# NRF24L01.net
KiCad netlist of a schematic drawn in Altium Designer
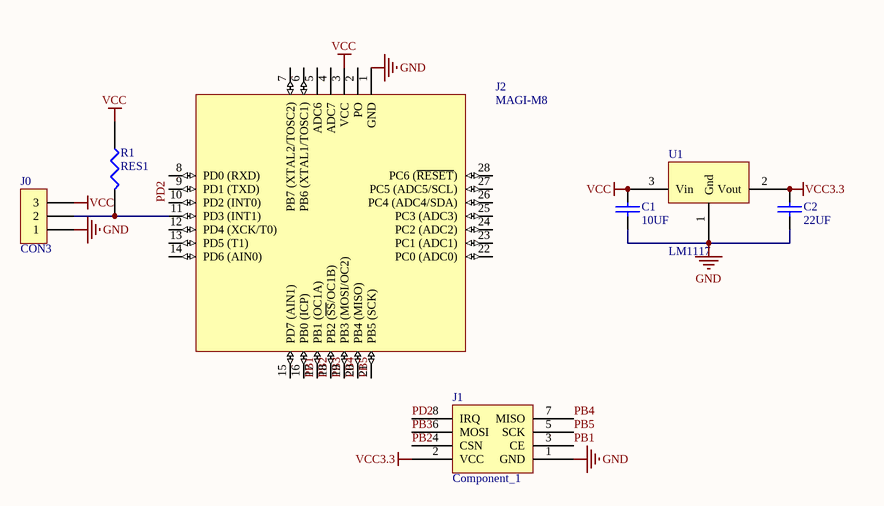
[diagram p0: NRF24L01.SchDoc]

(export (version "E")
  (design (tool "Eeschema 10.0.6"))
  (components
    (comp (ref "C1")
      (value "10UF")
      (footprint "0805")
      (description "Capacitor")
      (libsource (lib "电容器") (part "CAP_1"))
    )
    (comp (ref "C2")
      (value "22UF")
      (footprint "0805")
      (description "Capacitor")
      (libsource (lib "电容器") (part "CAP_1"))
    )
    (comp (ref "J0")
      (value "CON3")
      (footprint "CON3")
      (description "Connector")
      (libsource (lib "CON系列") (part "CON3"))
    )
    (comp (ref "J1")
      (value "Component_1")
      (footprint "NRF24L01")
      (libsource (lib "NRF24L01") (part "Component_1"))
    )
    (comp (ref "J2") (value "MAGI-M8") (footprint "MAGI-M8") (libsource (lib "MAGI-M8") (part "MAGI-M8")))
    (comp (ref "R1") (value "RES1") (footprint "0805") (libsource (lib "电阻器") (part "RES1")))
    (comp (ref "U1") (value "LM1117") (footprint "SOT-223") (libsource (lib "01.常用元件1") (part "LM1117")))
  )
  (nets
    (net (code "1") (name "/PB1") (class "Default")
      (node (ref "J1") (pin "3") (pinfunction "CE_3") (pintype "passive"))
      (node (ref "J2") (pin "17") (pinfunction "PB1_(OC1A)_17") (pintype "bidirectional"))
    )
    (net (code "2") (name "/PB2") (class "Default")
      (node (ref "J1") (pin "4") (pinfunction "CSN_4") (pintype "passive"))
      (node (ref "J2") (pin "18") (pinfunction "PB2_(~{SS}/OC1B)_18") (pintype "bidirectional"))
    )
    (net (code "3") (name "/PB3") (class "Default")
      (node (ref "J1") (pin "6") (pinfunction "MOSI_6") (pintype "passive"))
      (node (ref "J2") (pin "19") (pinfunction "PB3_(MOSI/OC2)_19") (pintype "bidirectional"))
    )
    (net (code "4") (name "/PB4") (class "Default")
      (node (ref "J1") (pin "7") (pinfunction "MISO_7") (pintype "passive"))
      (node (ref "J2") (pin "20") (pinfunction "PB4_(MISO)_20") (pintype "bidirectional"))
    )
    (net (code "5") (name "/PB5") (class "Default")
      (node (ref "J1") (pin "5") (pinfunction "SCK_5") (pintype "passive"))
      (node (ref "J2") (pin "21") (pinfunction "PB5_(SCK)_21") (pintype "bidirectional"))
    )
    (net (code "6") (name "/PD2") (class "Default")
      (node (ref "J1") (pin "8") (pinfunction "IRQ_8") (pintype "passive"))
      (node (ref "J2") (pin "10") (pinfunction "PD2_(INT0)_10") (pintype "bidirectional"))
    )
    (net (code "7") (name "GND") (class "Default")
      (node (ref "C1") (pin "2") (pinfunction "2_2") (pintype "passive"))
      (node (ref "C2") (pin "2") (pinfunction "2_2") (pintype "passive"))
      (node (ref "J0") (pin "1") (pinfunction "1_1") (pintype "passive"))
      (node (ref "J1") (pin "1") (pinfunction "GND_1") (pintype "passive"))
      (node (ref "J2") (pin "1") (pinfunction "GND_1") (pintype "power_in"))
      (node (ref "U1") (pin "1") (pinfunction "Gnd_1") (pintype "passive"))
    )
    (net (code "8") (name "Net-(J2-PD3_(INT1))") (class "Default")
      (node (ref "J0") (pin "2") (pinfunction "2_2") (pintype "passive"))
      (node (ref "J2") (pin "11") (pinfunction "PD3_(INT1)_11") (pintype "bidirectional"))
      (node (ref "R1") (pin "2") (pinfunction "2_2") (pintype "passive"))
    )
    (net (code "9") (name "VCC") (class "Default")
      (node (ref "C1") (pin "1") (pinfunction "1_1") (pintype "passive"))
      (node (ref "J0") (pin "3") (pinfunction "3_3") (pintype "passive"))
      (node (ref "J2") (pin "3") (pinfunction "VCC_3") (pintype "power_in"))
      (node (ref "R1") (pin "1") (pinfunction "1_1") (pintype "passive"))
      (node (ref "U1") (pin "3") (pinfunction "Vin_3") (pintype "passive"))
    )
    (net (code "10") (name "VCC3.3") (class "Default")
      (node (ref "C2") (pin "1") (pinfunction "1_1") (pintype "passive"))
      (node (ref "J1") (pin "2") (pinfunction "VCC_2") (pintype "passive"))
      (node (ref "U1") (pin "2") (pinfunction "Vout_2") (pintype "passive"))
    )
    (net (code "11") (name "unconnected-(J2-ADC6-Pad5)") (class "Default")
      (node (ref "J2") (pin "5") (pinfunction "ADC6_5") (pintype "passive"))
    )
    (net (code "12") (name "unconnected-(J2-ADC7-Pad4)") (class "Default")
      (node (ref "J2") (pin "4") (pinfunction "ADC7_4") (pintype "passive"))
    )
    (net (code "13") (name "unconnected-(J2-PB0_(ICP)-Pad16)") (class "Default")
      (node (ref "J2") (pin "16") (pinfunction "PB0_(ICP)_16") (pintype "bidirectional"))
    )
    (net (code "14") (name "unconnected-(J2-PB6_(XTAL1{slash}TOSC1)-Pad6)") (class "Default")
      (node (ref "J2") (pin "6") (pinfunction "PB6_(XTAL1/TOSC1)_6") (pintype "bidirectional"))
    )
    (net (code "15") (name "unconnected-(J2-PB7_(XTAL2{slash}TOSC2)-Pad7)") (class "Default")
      (node (ref "J2") (pin "7") (pinfunction "PB7_(XTAL2/TOSC2)_7") (pintype "bidirectional"))
    )
    (net (code "16") (name "unconnected-(J2-PC0_(ADC0)-Pad22)") (class "Default")
      (node (ref "J2") (pin "22") (pinfunction "PC0_(ADC0)_22") (pintype "bidirectional"))
    )
    (net (code "17") (name "unconnected-(J2-PC1_(ADC1)-Pad23)") (class "Default")
      (node (ref "J2") (pin "23") (pinfunction "PC1_(ADC1)_23") (pintype "bidirectional"))
    )
    (net (code "18") (name "unconnected-(J2-PC2_(ADC2)-Pad24)") (class "Default")
      (node (ref "J2") (pin "24") (pinfunction "PC2_(ADC2)_24") (pintype "bidirectional"))
    )
    (net (code "19") (name "unconnected-(J2-PC3_(ADC3)-Pad25)") (class "Default")
      (node (ref "J2") (pin "25") (pinfunction "PC3_(ADC3)_25") (pintype "bidirectional"))
    )
    (net (code "20") (name "unconnected-(J2-PC4_(ADC4{slash}SDA)-Pad26)") (class "Default")
      (node (ref "J2") (pin "26") (pinfunction "PC4_(ADC4/SDA)_26") (pintype "bidirectional"))
    )
    (net (code "21") (name "unconnected-(J2-PC5_(ADC5{slash}SCL)-Pad27)") (class "Default")
      (node (ref "J2") (pin "27") (pinfunction "PC5_(ADC5/SCL)_27") (pintype "bidirectional"))
    )
    (net (code "22") (name "unconnected-(J2-PC6_(~{RESET})-Pad28)") (class "Default")
      (node (ref "J2") (pin "28") (pinfunction "PC6_(~{RESET})_28") (pintype "bidirectional"))
    )
    (net (code "23") (name "unconnected-(J2-PD0_(RXD)-Pad8)") (class "Default")
      (node (ref "J2") (pin "8") (pinfunction "PD0_(RXD)_8") (pintype "bidirectional"))
    )
    (net (code "24") (name "unconnected-(J2-PD1_(TXD)-Pad9)") (class "Default")
      (node (ref "J2") (pin "9") (pinfunction "PD1_(TXD)_9") (pintype "bidirectional"))
    )
    (net (code "25") (name "unconnected-(J2-PD4_(XCK{slash}T0)-Pad12)") (class "Default")
      (node (ref "J2") (pin "12") (pinfunction "PD4_(XCK/T0)_12") (pintype "bidirectional"))
    )
    (net (code "26") (name "unconnected-(J2-PD5_(T1)-Pad13)") (class "Default")
      (node (ref "J2") (pin "13") (pinfunction "PD5_(T1)_13") (pintype "bidirectional"))
    )
    (net (code "27") (name "unconnected-(J2-PD6_(AIN0)-Pad14)") (class "Default")
      (node (ref "J2") (pin "14") (pinfunction "PD6_(AIN0)_14") (pintype "bidirectional"))
    )
    (net (code "28") (name "unconnected-(J2-PD7_(AIN1)-Pad15)") (class "Default")
      (node (ref "J2") (pin "15") (pinfunction "PD7_(AIN1)_15") (pintype "bidirectional"))
    )
    (net (code "29") (name "unconnected-(J2-PO-Pad2)") (class "Default")
      (node (ref "J2") (pin "2") (pinfunction "PO_2") (pintype "power_in"))
    )
  )
)
